# Connectors.net
KiCad netlist of a schematic drawn in Altium Designer
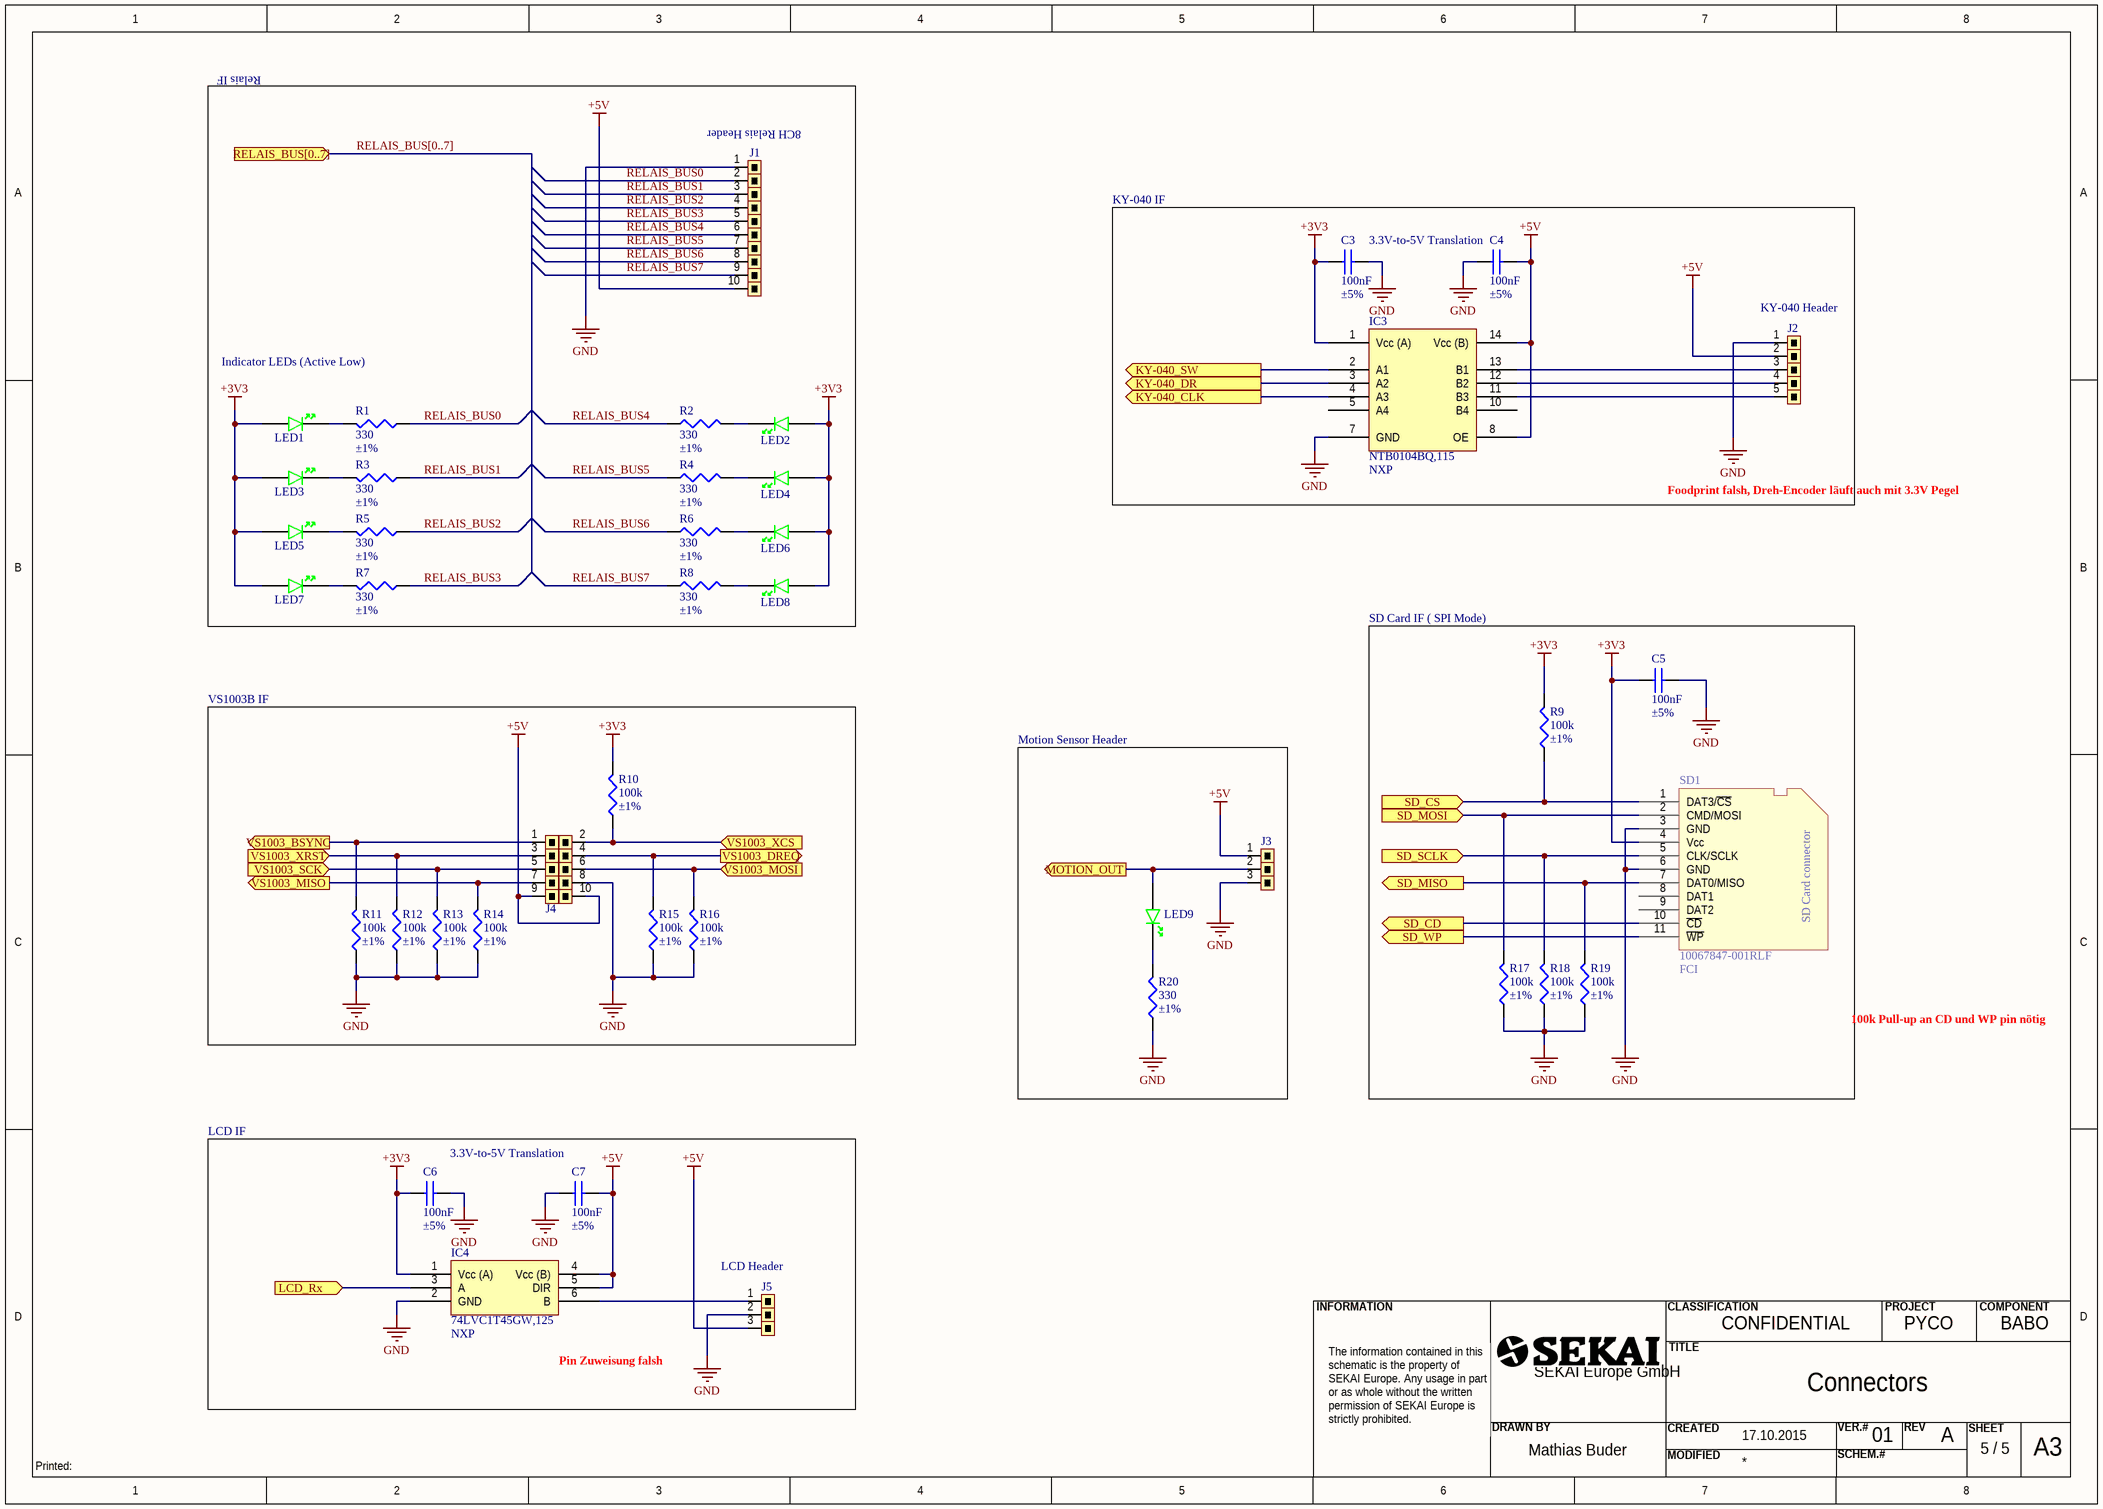
[diagram p0: Connectors.SchDoc]

(export (version "E")
  (design (tool "Eeschema 10.0.6"))
  (components
    (comp (ref "C3")
      (value "C0603C104J4RACTU")
      (footprint "C0603")
      (description "CAP CER 100NF 16V 5% X7R 0603")
      (fields
        (field (name "MANUFACTURER") "Kemet")
        (field (name "KAPAZITÄT") "100nF")
        (field (name "TOLERANZ") "±5%")
      )
      (libsource (lib "CAP") (part "C0603C104J4RACTU"))
    )
    (comp (ref "C4")
      (value "C0603C104J4RACTU")
      (footprint "C0603")
      (description "CAP CER 100NF 16V 5% X7R 0603")
      (fields
        (field (name "MANUFACTURER") "Kemet")
        (field (name "KAPAZITÄT") "100nF")
        (field (name "TOLERANZ") "±5%")
      )
      (libsource (lib "CAP") (part "C0603C104J4RACTU"))
    )
    (comp (ref "C5")
      (value "C0603C104J4RACTU")
      (footprint "C0603")
      (description "CAP CER 100NF 16V 5% X7R 0603")
      (fields
        (field (name "MANUFACTURER") "Kemet")
        (field (name "KAPAZITÄT") "100nF")
        (field (name "TOLERANZ") "±5%")
      )
      (libsource (lib "CAP") (part "C0603C104J4RACTU"))
    )
    (comp (ref "C6")
      (value "C0603C104J4RACTU")
      (footprint "C0603")
      (description "CAP CER 100NF 16V 5% X7R 0603")
      (fields
        (field (name "MANUFACTURER") "Kemet")
        (field (name "KAPAZITÄT") "100nF")
        (field (name "TOLERANZ") "±5%")
      )
      (libsource (lib "CAP") (part "C0603C104J4RACTU"))
    )
    (comp (ref "C7")
      (value "C0603C104J4RACTU")
      (footprint "C0603")
      (description "CAP CER 100NF 16V 5% X7R 0603")
      (fields
        (field (name "MANUFACTURER") "Kemet")
        (field (name "KAPAZITÄT") "100nF")
        (field (name "TOLERANZ") "±5%")
      )
      (libsource (lib "CAP") (part "C0603C104J4RACTU"))
    )
    (comp (ref "IC3")
      (value "NTB0104BQ,115")
      (footprint "QFN14")
      (description "TXRX TRANSLATING 3STATE 14DHVQFN")
      (fields (field (name "MANUFACTURER") "NXP"))
      (libsource (lib "TRANSLA_NXP") (part "NTB0104BQ,115"))
    )
    (comp (ref "IC4")
      (value "74LVC1T45GW,125")
      (footprint "SOT363")
      (description "TXRX XLATING DUAL 3ST 6TSSOP")
      (fields (field (name "MANUFACTURER") "NXP"))
      (libsource (lib "TRANSLA_NXP") (part "74LVC1T45GW,125"))
    )
    (comp (ref "J1")
      (value "Header 1x10")
      (footprint "Post Height Terminal Strip 1x10")
      (libsource (lib "CON_Standard") (part "Header 1x10"))
    )
    (comp (ref "J2")
      (value "Header 1x5")
      (footprint "Post Height Terminal Strip 1x5")
      (libsource (lib "CON_Standard") (part "Header 1x5"))
    )
    (comp (ref "J3")
      (value "1x3")
      (footprint "Post Height Terminal Strip 1x3")
      (libsource (lib "CON_Standard") (part "Header 1x3"))
    )
    (comp (ref "J4")
      (value "Header 2x5")
      (footprint "Post Height Terminal Strip 2x5")
      (libsource (lib "CON_Standard") (part "Header 2x5"))
    )
    (comp (ref "J5")
      (value "1x3")
      (footprint "Post Height Terminal Strip 1x3")
      (libsource (lib "CON_Standard") (part "Header 1x3"))
    )
    (comp (ref "LED1")
      (value "LTST-C193KGKT-5A")
      (footprint "LED0603-GREEN")
      (description "LED GREEN CLEAR 0603 SMD")
      (fields (field (name "MANUFACTURER") "Lite-On Inc."))
      (libsource (lib "LED_Standard") (part "LTST-C193KGKT-5A"))
    )
    (comp (ref "LED2")
      (value "LTST-C193KGKT-5A")
      (footprint "LED0603-GREEN")
      (description "LED GREEN CLEAR 0603 SMD")
      (fields (field (name "MANUFACTURER") "Lite-On Inc."))
      (libsource (lib "LED_Standard") (part "LTST-C193KGKT-5A"))
    )
    (comp (ref "LED3")
      (value "LTST-C193KGKT-5A")
      (footprint "LED0603-GREEN")
      (description "LED GREEN CLEAR 0603 SMD")
      (fields (field (name "MANUFACTURER") "Lite-On Inc."))
      (libsource (lib "LED_Standard") (part "LTST-C193KGKT-5A"))
    )
    (comp (ref "LED4")
      (value "LTST-C193KGKT-5A")
      (footprint "LED0603-GREEN")
      (description "LED GREEN CLEAR 0603 SMD")
      (fields (field (name "MANUFACTURER") "Lite-On Inc."))
      (libsource (lib "LED_Standard") (part "LTST-C193KGKT-5A"))
    )
    (comp (ref "LED5")
      (value "LTST-C193KGKT-5A")
      (footprint "LED0603-GREEN")
      (description "LED GREEN CLEAR 0603 SMD")
      (fields (field (name "MANUFACTURER") "Lite-On Inc."))
      (libsource (lib "LED_Standard") (part "LTST-C193KGKT-5A"))
    )
    (comp (ref "LED6")
      (value "LTST-C193KGKT-5A")
      (footprint "LED0603-GREEN")
      (description "LED GREEN CLEAR 0603 SMD")
      (fields (field (name "MANUFACTURER") "Lite-On Inc."))
      (libsource (lib "LED_Standard") (part "LTST-C193KGKT-5A"))
    )
    (comp (ref "LED7")
      (value "LTST-C193KGKT-5A")
      (footprint "LED0603-GREEN")
      (description "LED GREEN CLEAR 0603 SMD")
      (fields (field (name "MANUFACTURER") "Lite-On Inc."))
      (libsource (lib "LED_Standard") (part "LTST-C193KGKT-5A"))
    )
    (comp (ref "LED8")
      (value "LTST-C193KGKT-5A")
      (footprint "LED0603-GREEN")
      (description "LED GREEN CLEAR 0603 SMD")
      (fields (field (name "MANUFACTURER") "Lite-On Inc."))
      (libsource (lib "LED_Standard") (part "LTST-C193KGKT-5A"))
    )
    (comp (ref "LED9")
      (value "LTST-C193KGKT-5A")
      (footprint "LED0603-GREEN")
      (description "LED GREEN CLEAR 0603 SMD")
      (fields (field (name "MANUFACTURER") "Lite-On Inc."))
      (libsource (lib "LED_Standard") (part "LTST-C193KGKT-5A"))
    )
    (comp (ref "R1")
      (value "ERJ-3EKF3300V")
      (footprint "R0603")
      (description "RES SMD 330 OHM 1% 1/10W 0603")
      (fields
        (field (name "MANUFACTURER") "Panasonic Electronic Components")
        (field (name "RESISTANCE (OHMS)") "330")
        (field (name "TOLERANCE") "±1%")
      )
      (libsource (lib "RES") (part "ERJ-3EKF3300V"))
    )
    (comp (ref "R2")
      (value "ERJ-3EKF3300V")
      (footprint "R0603")
      (description "RES SMD 330 OHM 1% 1/10W 0603")
      (fields
        (field (name "MANUFACTURER") "Panasonic Electronic Components")
        (field (name "RESISTANCE (OHMS)") "330")
        (field (name "TOLERANCE") "±1%")
      )
      (libsource (lib "RES") (part "ERJ-3EKF3300V"))
    )
    (comp (ref "R3")
      (value "ERJ-3EKF3300V")
      (footprint "R0603")
      (description "RES SMD 330 OHM 1% 1/10W 0603")
      (fields
        (field (name "MANUFACTURER") "Panasonic Electronic Components")
        (field (name "RESISTANCE (OHMS)") "330")
        (field (name "TOLERANCE") "±1%")
      )
      (libsource (lib "RES") (part "ERJ-3EKF3300V"))
    )
    (comp (ref "R4")
      (value "ERJ-3EKF3300V")
      (footprint "R0603")
      (description "RES SMD 330 OHM 1% 1/10W 0603")
      (fields
        (field (name "MANUFACTURER") "Panasonic Electronic Components")
        (field (name "RESISTANCE (OHMS)") "330")
        (field (name "TOLERANCE") "±1%")
      )
      (libsource (lib "RES") (part "ERJ-3EKF3300V"))
    )
    (comp (ref "R5")
      (value "ERJ-3EKF3300V")
      (footprint "R0603")
      (description "RES SMD 330 OHM 1% 1/10W 0603")
      (fields
        (field (name "MANUFACTURER") "Panasonic Electronic Components")
        (field (name "RESISTANCE (OHMS)") "330")
        (field (name "TOLERANCE") "±1%")
      )
      (libsource (lib "RES") (part "ERJ-3EKF3300V"))
    )
    (comp (ref "R6")
      (value "ERJ-3EKF3300V")
      (footprint "R0603")
      (description "RES SMD 330 OHM 1% 1/10W 0603")
      (fields
        (field (name "MANUFACTURER") "Panasonic Electronic Components")
        (field (name "RESISTANCE (OHMS)") "330")
        (field (name "TOLERANCE") "±1%")
      )
      (libsource (lib "RES") (part "ERJ-3EKF3300V"))
    )
    (comp (ref "R7")
      (value "ERJ-3EKF3300V")
      (footprint "R0603")
      (description "RES SMD 330 OHM 1% 1/10W 0603")
      (fields
        (field (name "MANUFACTURER") "Panasonic Electronic Components")
        (field (name "RESISTANCE (OHMS)") "330")
        (field (name "TOLERANCE") "±1%")
      )
      (libsource (lib "RES") (part "ERJ-3EKF3300V"))
    )
    (comp (ref "R8")
      (value "ERJ-3EKF3300V")
      (footprint "R0603")
      (description "RES SMD 330 OHM 1% 1/10W 0603")
      (fields
        (field (name "MANUFACTURER") "Panasonic Electronic Components")
        (field (name "RESISTANCE (OHMS)") "330")
        (field (name "TOLERANCE") "±1%")
      )
      (libsource (lib "RES") (part "ERJ-3EKF3300V"))
    )
    (comp (ref "R9")
      (value "ERJ-3EKF1003V")
      (footprint "R0603")
      (description "RES SMD 100K OHM 1% 1/10W 0603")
      (fields
        (field (name "MANUFACTURER") "Panasonic Electronic Components")
        (field (name "RESISTANCE (OHMS)") "100k")
        (field (name "TOLERANCE") "±1%")
      )
      (libsource (lib "RES") (part "ERJ-3EKF1003V"))
    )
    (comp (ref "R10")
      (value "ERJ-3EKF1003V")
      (footprint "R0603")
      (description "RES SMD 100K OHM 1% 1/10W 0603")
      (fields
        (field (name "MANUFACTURER") "Panasonic Electronic Components")
        (field (name "RESISTANCE (OHMS)") "100k")
        (field (name "TOLERANCE") "±1%")
      )
      (libsource (lib "RES") (part "ERJ-3EKF1003V"))
    )
    (comp (ref "R11")
      (value "ERJ-3EKF1003V")
      (footprint "R0603")
      (description "RES SMD 100K OHM 1% 1/10W 0603")
      (fields
        (field (name "MANUFACTURER") "Panasonic Electronic Components")
        (field (name "RESISTANCE (OHMS)") "100k")
        (field (name "TOLERANCE") "±1%")
      )
      (libsource (lib "RES") (part "ERJ-3EKF1003V"))
    )
    (comp (ref "R12")
      (value "ERJ-3EKF1003V")
      (footprint "R0603")
      (description "RES SMD 100K OHM 1% 1/10W 0603")
      (fields
        (field (name "MANUFACTURER") "Panasonic Electronic Components")
        (field (name "RESISTANCE (OHMS)") "100k")
        (field (name "TOLERANCE") "±1%")
      )
      (libsource (lib "RES") (part "ERJ-3EKF1003V"))
    )
    (comp (ref "R13")
      (value "ERJ-3EKF1003V")
      (footprint "R0603")
      (description "RES SMD 100K OHM 1% 1/10W 0603")
      (fields
        (field (name "MANUFACTURER") "Panasonic Electronic Components")
        (field (name "RESISTANCE (OHMS)") "100k")
        (field (name "TOLERANCE") "±1%")
      )
      (libsource (lib "RES") (part "ERJ-3EKF1003V"))
    )
    (comp (ref "R14")
      (value "ERJ-3EKF1003V")
      (footprint "R0603")
      (description "RES SMD 100K OHM 1% 1/10W 0603")
      (fields
        (field (name "MANUFACTURER") "Panasonic Electronic Components")
        (field (name "RESISTANCE (OHMS)") "100k")
        (field (name "TOLERANCE") "±1%")
      )
      (libsource (lib "RES") (part "ERJ-3EKF1003V"))
    )
    (comp (ref "R15")
      (value "ERJ-3EKF1003V")
      (footprint "R0603")
      (description "RES SMD 100K OHM 1% 1/10W 0603")
      (fields
        (field (name "MANUFACTURER") "Panasonic Electronic Components")
        (field (name "RESISTANCE (OHMS)") "100k")
        (field (name "TOLERANCE") "±1%")
      )
      (libsource (lib "RES") (part "ERJ-3EKF1003V"))
    )
    (comp (ref "R16")
      (value "ERJ-3EKF1003V")
      (footprint "R0603")
      (description "RES SMD 100K OHM 1% 1/10W 0603")
      (fields
        (field (name "MANUFACTURER") "Panasonic Electronic Components")
        (field (name "RESISTANCE (OHMS)") "100k")
        (field (name "TOLERANCE") "±1%")
      )
      (libsource (lib "RES") (part "ERJ-3EKF1003V"))
    )
    (comp (ref "R17")
      (value "ERJ-3EKF1003V")
      (footprint "R0603")
      (description "RES SMD 100K OHM 1% 1/10W 0603")
      (fields
        (field (name "MANUFACTURER") "Panasonic Electronic Components")
        (field (name "RESISTANCE (OHMS)") "100k")
        (field (name "TOLERANCE") "±1%")
      )
      (libsource (lib "RES") (part "ERJ-3EKF1003V"))
    )
    (comp (ref "R18")
      (value "ERJ-3EKF1003V")
      (footprint "R0603")
      (description "RES SMD 100K OHM 1% 1/10W 0603")
      (fields
        (field (name "MANUFACTURER") "Panasonic Electronic Components")
        (field (name "RESISTANCE (OHMS)") "100k")
        (field (name "TOLERANCE") "±1%")
      )
      (libsource (lib "RES") (part "ERJ-3EKF1003V"))
    )
    (comp (ref "R19")
      (value "ERJ-3EKF1003V")
      (footprint "R0603")
      (description "RES SMD 100K OHM 1% 1/10W 0603")
      (fields
        (field (name "MANUFACTURER") "Panasonic Electronic Components")
        (field (name "RESISTANCE (OHMS)") "100k")
        (field (name "TOLERANCE") "±1%")
      )
      (libsource (lib "RES") (part "ERJ-3EKF1003V"))
    )
    (comp (ref "R20")
      (value "ERJ-3EKF3300V")
      (footprint "R0603")
      (description "RES SMD 330 OHM 1% 1/10W 0603")
      (fields
        (field (name "MANUFACTURER") "Panasonic Electronic Components")
        (field (name "RESISTANCE (OHMS)") "330")
        (field (name "TOLERANCE") "±1%")
      )
      (libsource (lib "RES") (part "ERJ-3EKF3300V"))
    )
    (comp (ref "SD1")
      (value "10067847-001RLF")
      (footprint "10067847-001RLF")
      (description "CONN SD CARD PUSH-PUSH SMD")
      (fields (field (name "MANUFACTURER") "FCI"))
      (libsource (lib "SD_FCI") (part "10067847-001RLF"))
    )
  )
  (nets
    (net (code "1") (name "+3V3") (class "Default")
      (node (ref "C3") (pin "1") (pinfunction "1_1") (pintype "passive"))
      (node (ref "C5") (pin "1") (pinfunction "1_1") (pintype "passive"))
      (node (ref "C6") (pin "1") (pinfunction "1_1") (pintype "passive"))
      (node (ref "IC3") (pin "1") (pinfunction "Vcc_(A)_1") (pintype "passive"))
      (node (ref "IC4") (pin "1") (pinfunction "Vcc_(A)_1") (pintype "passive"))
      (node (ref "LED1") (pin "1") (pinfunction "ANODE_1") (pintype "passive"))
      (node (ref "LED2") (pin "1") (pinfunction "ANODE_1") (pintype "passive"))
      (node (ref "LED3") (pin "1") (pinfunction "ANODE_1") (pintype "passive"))
      (node (ref "LED4") (pin "1") (pinfunction "ANODE_1") (pintype "passive"))
      (node (ref "LED5") (pin "1") (pinfunction "ANODE_1") (pintype "passive"))
      (node (ref "LED6") (pin "1") (pinfunction "ANODE_1") (pintype "passive"))
      (node (ref "LED7") (pin "1") (pinfunction "ANODE_1") (pintype "passive"))
      (node (ref "LED8") (pin "1") (pinfunction "ANODE_1") (pintype "passive"))
      (node (ref "R10") (pin "2") (pinfunction "2_2") (pintype "passive"))
      (node (ref "R9") (pin "2") (pinfunction "2_2") (pintype "passive"))
      (node (ref "SD1") (pin "4") (pinfunction "Vcc_4") (pintype "passive"))
    )
    (net (code "2") (name "+5V") (class "Default")
      (node (ref "C4") (pin "2") (pinfunction "2_2") (pintype "passive"))
      (node (ref "C7") (pin "2") (pinfunction "2_2") (pintype "passive"))
      (node (ref "IC3") (pin "14") (pinfunction "Vcc_(B)_14") (pintype "passive"))
      (node (ref "IC3") (pin "8") (pinfunction "OE_8") (pintype "passive"))
      (node (ref "IC4") (pin "4") (pinfunction "Vcc_(B)_4") (pintype "passive"))
      (node (ref "IC4") (pin "5") (pinfunction "DIR_5") (pintype "passive"))
      (node (ref "J1") (pin "10") (pinfunction "10_10") (pintype "passive"))
      (node (ref "J2") (pin "2") (pinfunction "2_2") (pintype "passive"))
      (node (ref "J3") (pin "1") (pinfunction "1_1") (pintype "passive"))
      (node (ref "J4") (pin "10") (pinfunction "10_10") (pintype "passive"))
      (node (ref "J4") (pin "9") (pinfunction "9_9") (pintype "passive"))
      (node (ref "J5") (pin "3") (pinfunction "3_3") (pintype "passive"))
    )
    (net (code "3") (name "/KY-040_CLK") (class "Default")
      (node (ref "IC3") (pin "4") (pinfunction "A3_4") (pintype "passive"))
    )
    (net (code "4") (name "/KY-040_DR") (class "Default")
      (node (ref "IC3") (pin "3") (pinfunction "A2_3") (pintype "passive"))
    )
    (net (code "5") (name "/KY-040_SW") (class "Default")
      (node (ref "IC3") (pin "2") (pinfunction "A1_2") (pintype "passive"))
    )
    (net (code "6") (name "/LCD_Rx") (class "Default")
      (node (ref "IC4") (pin "3") (pinfunction "A_3") (pintype "passive"))
    )
    (net (code "7") (name "/MOTION_OUT") (class "Default")
      (node (ref "J3") (pin "2") (pinfunction "2_2") (pintype "passive"))
      (node (ref "LED9") (pin "1") (pinfunction "ANODE_1") (pintype "passive"))
    )
    (net (code "8") (name "/RELAIS_BUS0") (class "Default")
      (node (ref "J1") (pin "2") (pinfunction "2_2") (pintype "passive"))
      (node (ref "R1") (pin "1") (pinfunction "1_1") (pintype "passive"))
    )
    (net (code "9") (name "/RELAIS_BUS1") (class "Default")
      (node (ref "J1") (pin "3") (pinfunction "3_3") (pintype "passive"))
      (node (ref "R3") (pin "1") (pinfunction "1_1") (pintype "passive"))
    )
    (net (code "10") (name "/RELAIS_BUS2") (class "Default")
      (node (ref "J1") (pin "4") (pinfunction "4_4") (pintype "passive"))
      (node (ref "R5") (pin "1") (pinfunction "1_1") (pintype "passive"))
    )
    (net (code "11") (name "/RELAIS_BUS3") (class "Default")
      (node (ref "J1") (pin "5") (pinfunction "5_5") (pintype "passive"))
      (node (ref "R7") (pin "1") (pinfunction "1_1") (pintype "passive"))
    )
    (net (code "12") (name "/RELAIS_BUS4") (class "Default")
      (node (ref "J1") (pin "6") (pinfunction "6_6") (pintype "passive"))
      (node (ref "R2") (pin "1") (pinfunction "1_1") (pintype "passive"))
    )
    (net (code "13") (name "/RELAIS_BUS5") (class "Default")
      (node (ref "J1") (pin "7") (pinfunction "7_7") (pintype "passive"))
      (node (ref "R4") (pin "1") (pinfunction "1_1") (pintype "passive"))
    )
    (net (code "14") (name "/RELAIS_BUS6") (class "Default")
      (node (ref "J1") (pin "8") (pinfunction "8_8") (pintype "passive"))
      (node (ref "R6") (pin "1") (pinfunction "1_1") (pintype "passive"))
    )
    (net (code "15") (name "/RELAIS_BUS7") (class "Default")
      (node (ref "J1") (pin "9") (pinfunction "9_9") (pintype "passive"))
      (node (ref "R8") (pin "1") (pinfunction "1_1") (pintype "passive"))
    )
    (net (code "17") (name "/SD_CD") (class "Default")
      (node (ref "SD1") (pin "10") (pinfunction "~{CD}_10") (pintype "passive"))
    )
    (net (code "18") (name "/SD_CS") (class "Default")
      (node (ref "R9") (pin "1") (pinfunction "1_1") (pintype "passive"))
      (node (ref "SD1") (pin "1") (pinfunction "DAT3/~{CS}_1") (pintype "passive"))
    )
    (net (code "19") (name "/SD_MISO") (class "Default")
      (node (ref "R19") (pin "2") (pinfunction "2_2") (pintype "passive"))
      (node (ref "SD1") (pin "7") (pinfunction "DAT0/MISO_7") (pintype "passive"))
    )
    (net (code "20") (name "/SD_MOSI") (class "Default")
      (node (ref "R17") (pin "2") (pinfunction "2_2") (pintype "passive"))
      (node (ref "SD1") (pin "2") (pinfunction "CMD/MOSI_2") (pintype "passive"))
    )
    (net (code "21") (name "/SD_SCLK") (class "Default")
      (node (ref "R18") (pin "2") (pinfunction "2_2") (pintype "passive"))
      (node (ref "SD1") (pin "5") (pinfunction "CLK/SCLK_5") (pintype "passive"))
    )
    (net (code "22") (name "/SD_WP") (class "Default")
      (node (ref "SD1") (pin "11") (pinfunction "~{WP}_11") (pintype "passive"))
    )
    (net (code "23") (name "/VS1003_BSYNC") (class "Default")
      (node (ref "J4") (pin "1") (pinfunction "1_1") (pintype "passive"))
      (node (ref "R11") (pin "2") (pinfunction "2_2") (pintype "passive"))
    )
    (net (code "24") (name "/VS1003_DREQ") (class "Default")
      (node (ref "J4") (pin "4") (pinfunction "4_4") (pintype "passive"))
      (node (ref "R15") (pin "2") (pinfunction "2_2") (pintype "passive"))
    )
    (net (code "25") (name "/VS1003_MISO") (class "Default")
      (node (ref "J4") (pin "7") (pinfunction "7_7") (pintype "passive"))
      (node (ref "R14") (pin "2") (pinfunction "2_2") (pintype "passive"))
    )
    (net (code "26") (name "/VS1003_MOSI") (class "Default")
      (node (ref "J4") (pin "6") (pinfunction "6_6") (pintype "passive"))
      (node (ref "R16") (pin "2") (pinfunction "2_2") (pintype "passive"))
    )
    (net (code "27") (name "/VS1003_SCK") (class "Default")
      (node (ref "J4") (pin "5") (pinfunction "5_5") (pintype "passive"))
      (node (ref "R13") (pin "2") (pinfunction "2_2") (pintype "passive"))
    )
    (net (code "28") (name "/VS1003_XCS") (class "Default")
      (node (ref "J4") (pin "2") (pinfunction "2_2") (pintype "passive"))
      (node (ref "R10") (pin "1") (pinfunction "1_1") (pintype "passive"))
    )
    (net (code "29") (name "/VS1003_XRST") (class "Default")
      (node (ref "J4") (pin "3") (pinfunction "3_3") (pintype "passive"))
      (node (ref "R12") (pin "2") (pinfunction "2_2") (pintype "passive"))
    )
    (net (code "30") (name "GND") (class "Default")
      (node (ref "C3") (pin "2") (pinfunction "2_2") (pintype "passive"))
      (node (ref "C4") (pin "1") (pinfunction "1_1") (pintype "passive"))
      (node (ref "C5") (pin "2") (pinfunction "2_2") (pintype "passive"))
      (node (ref "C6") (pin "2") (pinfunction "2_2") (pintype "passive"))
      (node (ref "C7") (pin "1") (pinfunction "1_1") (pintype "passive"))
      (node (ref "IC3") (pin "7") (pinfunction "GND_7") (pintype "passive"))
      (node (ref "IC4") (pin "2") (pinfunction "GND_2") (pintype "passive"))
      (node (ref "J1") (pin "1") (pinfunction "1_1") (pintype "passive"))
      (node (ref "J2") (pin "1") (pinfunction "1_1") (pintype "passive"))
      (node (ref "J3") (pin "3") (pinfunction "3_3") (pintype "passive"))
      (node (ref "J4") (pin "8") (pinfunction "8_8") (pintype "passive"))
      (node (ref "J5") (pin "2") (pinfunction "2_2") (pintype "passive"))
      (node (ref "R11") (pin "1") (pinfunction "1_1") (pintype "passive"))
      (node (ref "R12") (pin "1") (pinfunction "1_1") (pintype "passive"))
      (node (ref "R13") (pin "1") (pinfunction "1_1") (pintype "passive"))
      (node (ref "R14") (pin "1") (pinfunction "1_1") (pintype "passive"))
      (node (ref "R15") (pin "1") (pinfunction "1_1") (pintype "passive"))
      (node (ref "R16") (pin "1") (pinfunction "1_1") (pintype "passive"))
      (node (ref "R17") (pin "1") (pinfunction "1_1") (pintype "passive"))
      (node (ref "R18") (pin "1") (pinfunction "1_1") (pintype "passive"))
      (node (ref "R19") (pin "1") (pinfunction "1_1") (pintype "passive"))
      (node (ref "R20") (pin "1") (pinfunction "1_1") (pintype "passive"))
      (node (ref "SD1") (pin "3") (pinfunction "GND_3") (pintype "passive"))
      (node (ref "SD1") (pin "6") (pinfunction "GND_6") (pintype "passive"))
    )
    (net (code "31") (name "Net-(IC3-B1)") (class "Default")
      (node (ref "IC3") (pin "13") (pinfunction "B1_13") (pintype "passive"))
      (node (ref "J2") (pin "3") (pinfunction "3_3") (pintype "passive"))
    )
    (net (code "32") (name "Net-(IC3-B2)") (class "Default")
      (node (ref "IC3") (pin "12") (pinfunction "B2_12") (pintype "passive"))
      (node (ref "J2") (pin "4") (pinfunction "4_4") (pintype "passive"))
    )
    (net (code "33") (name "Net-(IC3-B3)") (class "Default")
      (node (ref "IC3") (pin "11") (pinfunction "B3_11") (pintype "passive"))
      (node (ref "J2") (pin "5") (pinfunction "5_5") (pintype "passive"))
    )
    (net (code "34") (name "Net-(IC4-B)") (class "Default")
      (node (ref "IC4") (pin "6") (pinfunction "B_6") (pintype "passive"))
      (node (ref "J5") (pin "1") (pinfunction "1_1") (pintype "passive"))
    )
    (net (code "35") (name "Net-(LED1-CATHODE)") (class "Default")
      (node (ref "LED1") (pin "2") (pinfunction "CATHODE_2") (pintype "passive"))
      (node (ref "R1") (pin "2") (pinfunction "2_2") (pintype "passive"))
    )
    (net (code "36") (name "Net-(LED2-CATHODE)") (class "Default")
      (node (ref "LED2") (pin "2") (pinfunction "CATHODE_2") (pintype "passive"))
      (node (ref "R2") (pin "2") (pinfunction "2_2") (pintype "passive"))
    )
    (net (code "37") (name "Net-(LED3-CATHODE)") (class "Default")
      (node (ref "LED3") (pin "2") (pinfunction "CATHODE_2") (pintype "passive"))
      (node (ref "R3") (pin "2") (pinfunction "2_2") (pintype "passive"))
    )
    (net (code "38") (name "Net-(LED4-CATHODE)") (class "Default")
      (node (ref "LED4") (pin "2") (pinfunction "CATHODE_2") (pintype "passive"))
      (node (ref "R4") (pin "2") (pinfunction "2_2") (pintype "passive"))
    )
    (net (code "39") (name "Net-(LED5-CATHODE)") (class "Default")
      (node (ref "LED5") (pin "2") (pinfunction "CATHODE_2") (pintype "passive"))
      (node (ref "R5") (pin "2") (pinfunction "2_2") (pintype "passive"))
    )
    (net (code "40") (name "Net-(LED6-CATHODE)") (class "Default")
      (node (ref "LED6") (pin "2") (pinfunction "CATHODE_2") (pintype "passive"))
      (node (ref "R6") (pin "2") (pinfunction "2_2") (pintype "passive"))
    )
    (net (code "41") (name "Net-(LED7-CATHODE)") (class "Default")
      (node (ref "LED7") (pin "2") (pinfunction "CATHODE_2") (pintype "passive"))
      (node (ref "R7") (pin "2") (pinfunction "2_2") (pintype "passive"))
    )
    (net (code "42") (name "Net-(LED8-CATHODE)") (class "Default")
      (node (ref "LED8") (pin "2") (pinfunction "CATHODE_2") (pintype "passive"))
      (node (ref "R8") (pin "2") (pinfunction "2_2") (pintype "passive"))
    )
    (net (code "43") (name "Net-(LED9-CATHODE)") (class "Default")
      (node (ref "LED9") (pin "2") (pinfunction "CATHODE_2") (pintype "passive"))
      (node (ref "R20") (pin "2") (pinfunction "2_2") (pintype "passive"))
    )
    (net (code "44") (name "unconnected-(IC3-A4-Pad5)") (class "Default")
      (node (ref "IC3") (pin "5") (pinfunction "A4_5") (pintype "passive"))
    )
    (net (code "45") (name "unconnected-(IC3-B4-Pad10)") (class "Default")
      (node (ref "IC3") (pin "10") (pinfunction "B4_10") (pintype "passive"))
    )
    (net (code "46") (name "unconnected-(SD1-DAT1-Pad8)") (class "Default")
      (node (ref "SD1") (pin "8") (pinfunction "DAT1_8") (pintype "passive"))
    )
    (net (code "47") (name "unconnected-(SD1-DAT2-Pad9)") (class "Default")
      (node (ref "SD1") (pin "9") (pinfunction "DAT2_9") (pintype "passive"))
    )
  )
)
